# Hardware.net
KiCad netlist of a schematic drawn in Altium Designer
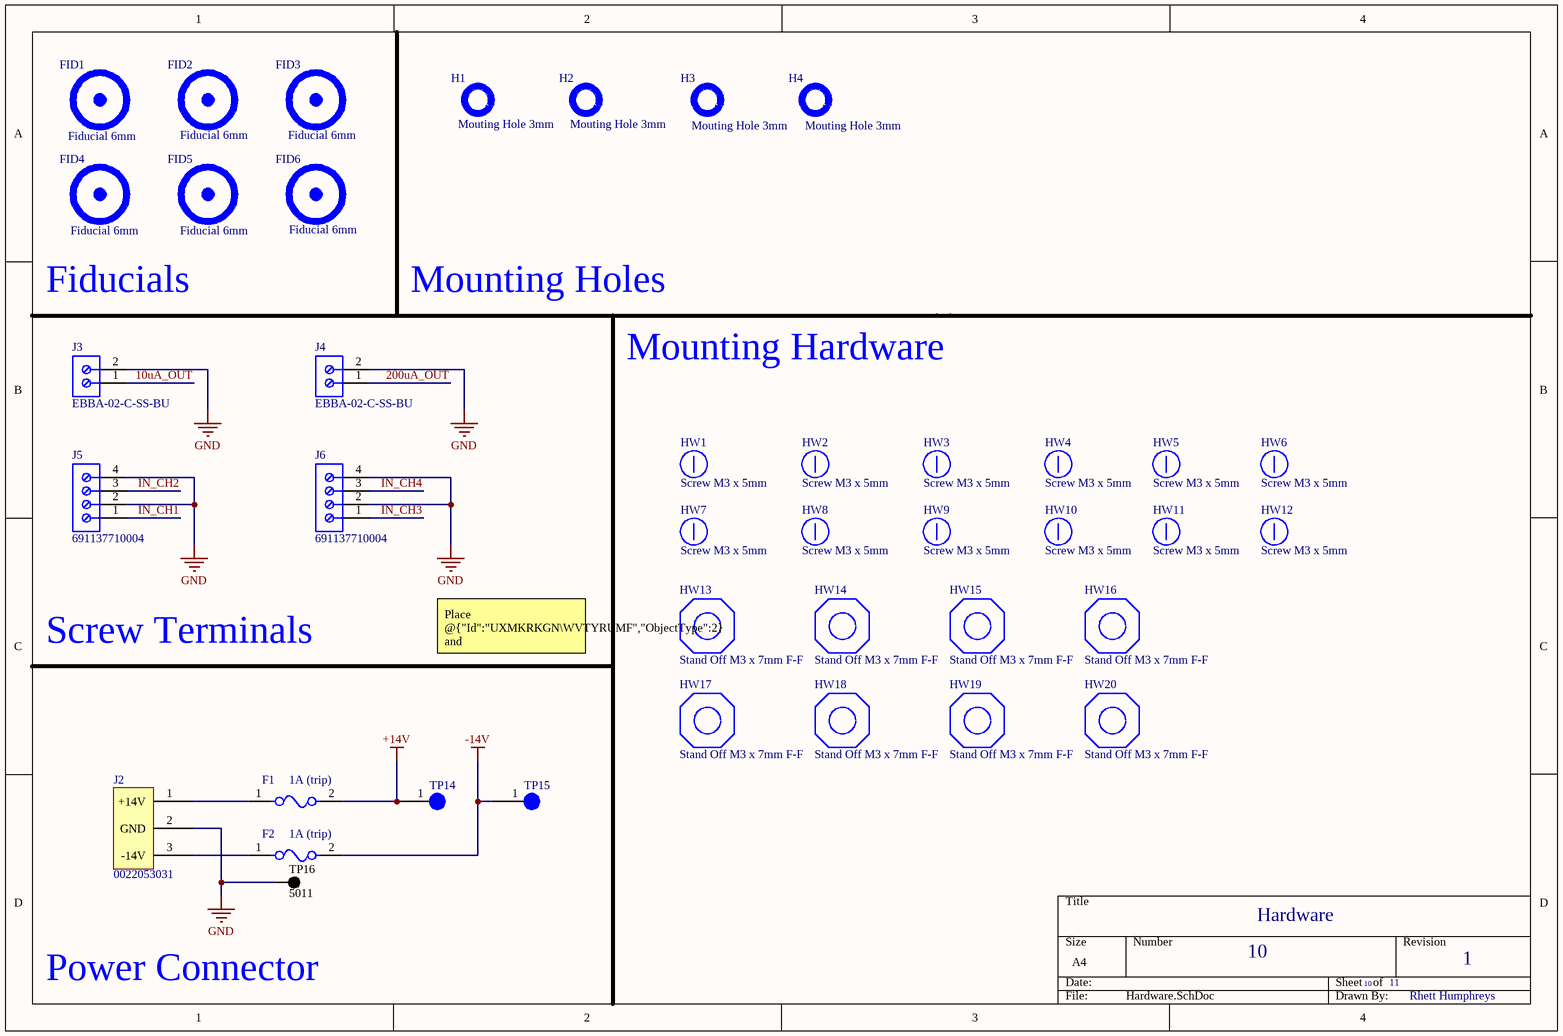
[diagram p0: Hardware.SchDoc]

(export (version "E")
  (design (tool "Eeschema 10.0.6"))
  (components
    (comp (ref "F1")
      (value "1A (trip)")
      (footprint "FP-0466-MFG")
      (description "FUSE BOARD MNT 1A 63VAC/VDC 1206")
      (fields
        (field (name "MANUFACTURER PART NUMBER") "0466001.NR")
        (field (name "MANUFACTURER") "Littelfuse Inc")
      )
      (libsource (lib "Altium Content Vault") (part "5bcf9b9f640e542cf0359d10258e979"))
    )
    (comp (ref "F2")
      (value "1A (trip)")
      (footprint "FP-0466-MFG")
      (description "FUSE BOARD MNT 1A 63VAC/VDC 1206")
      (fields
        (field (name "MANUFACTURER PART NUMBER") "0466001.NR")
        (field (name "MANUFACTURER") "Littelfuse Inc")
      )
      (libsource (lib "Altium Content Vault") (part "5bcf9b9f640e542cf0359d10258e979"))
    )
    (comp (ref "FID1")
      (value "Fiducial 6mm")
      (footprint "Fiducial 6mm")
      (libsource (lib "Master") (part "Fiducial 6mm"))
    )
    (comp (ref "FID2")
      (value "Fiducial 6mm")
      (footprint "Fiducial 6mm")
      (libsource (lib "Master") (part "Fiducial 6mm"))
    )
    (comp (ref "FID3")
      (value "Fiducial 6mm")
      (footprint "Fiducial 6mm")
      (libsource (lib "Master") (part "Fiducial 6mm"))
    )
    (comp (ref "FID4")
      (value "Fiducial 6mm")
      (footprint "Fiducial 6mm")
      (libsource (lib "Master") (part "Fiducial 6mm"))
    )
    (comp (ref "FID5")
      (value "Fiducial 6mm")
      (footprint "Fiducial 6mm")
      (libsource (lib "Master") (part "Fiducial 6mm"))
    )
    (comp (ref "FID6")
      (value "Fiducial 6mm")
      (footprint "Fiducial 6mm")
      (libsource (lib "Master") (part "Fiducial 6mm"))
    )
    (comp (ref "H1") (value "Mouting Hole 3mm") (footprint "MH3") (libsource (lib "Master") (part "MH3")))
    (comp (ref "H2") (value "Mouting Hole 3mm") (footprint "MH3") (libsource (lib "Master") (part "MH3")))
    (comp (ref "H3") (value "Mouting Hole 3mm") (footprint "MH3") (libsource (lib "Master") (part "MH3")))
    (comp (ref "H4") (value "Mouting Hole 3mm") (footprint "MH3") (libsource (lib "Master") (part "MH3")))
    (comp (ref "HW1")
      (value "Screw M3 x 5mm")
      (description "Fastener flathead M3 x 5mm")
      (libsource (lib "Master") (part "Screw M3 x 5mm"))
    )
    (comp (ref "HW2")
      (value "Screw M3 x 5mm")
      (description "Fastener flathead M3 x 5mm")
      (libsource (lib "Master") (part "Screw M3 x 5mm"))
    )
    (comp (ref "HW3")
      (value "Screw M3 x 5mm")
      (description "Fastener flathead M3 x 5mm")
      (libsource (lib "Master") (part "Screw M3 x 5mm"))
    )
    (comp (ref "HW4")
      (value "Screw M3 x 5mm")
      (description "Fastener flathead M3 x 5mm")
      (libsource (lib "Master") (part "Screw M3 x 5mm"))
    )
    (comp (ref "HW5")
      (value "Screw M3 x 5mm")
      (description "Fastener flathead M3 x 5mm")
      (libsource (lib "Master") (part "Screw M3 x 5mm"))
    )
    (comp (ref "HW6")
      (value "Screw M3 x 5mm")
      (description "Fastener flathead M3 x 5mm")
      (libsource (lib "Master") (part "Screw M3 x 5mm"))
    )
    (comp (ref "HW7")
      (value "Screw M3 x 5mm")
      (description "Fastener flathead M3 x 5mm")
      (libsource (lib "Master") (part "Screw M3 x 5mm"))
    )
    (comp (ref "HW8")
      (value "Screw M3 x 5mm")
      (description "Fastener flathead M3 x 5mm")
      (libsource (lib "Master") (part "Screw M3 x 5mm"))
    )
    (comp (ref "HW9")
      (value "Screw M3 x 5mm")
      (description "Fastener flathead M3 x 5mm")
      (libsource (lib "Master") (part "Screw M3 x 5mm"))
    )
    (comp (ref "HW10")
      (value "Screw M3 x 5mm")
      (description "Fastener flathead M3 x 5mm")
      (libsource (lib "Master") (part "Screw M3 x 5mm"))
    )
    (comp (ref "HW11")
      (value "Screw M3 x 5mm")
      (description "Fastener flathead M3 x 5mm")
      (libsource (lib "Master") (part "Screw M3 x 5mm"))
    )
    (comp (ref "HW12")
      (value "Screw M3 x 5mm")
      (description "Fastener flathead M3 x 5mm")
      (libsource (lib "Master") (part "Screw M3 x 5mm"))
    )
    (comp (ref "HW13")
      (value "Stand Off M3 x 7mm F-F")
      (description "Stand off hex M3 x 7mm")
      (libsource (lib "Master") (part "Stand Off M3 x 7mm F-F"))
    )
    (comp (ref "HW14")
      (value "Stand Off M3 x 7mm F-F")
      (description "Stand off hex M3 x 7mm")
      (libsource (lib "Master") (part "Stand Off M3 x 7mm F-F"))
    )
    (comp (ref "HW15")
      (value "Stand Off M3 x 7mm F-F")
      (description "Stand off hex M3 x 7mm")
      (libsource (lib "Master") (part "Stand Off M3 x 7mm F-F"))
    )
    (comp (ref "HW16")
      (value "Stand Off M3 x 7mm F-F")
      (description "Stand off hex M3 x 7mm")
      (libsource (lib "Master") (part "Stand Off M3 x 7mm F-F"))
    )
    (comp (ref "HW17")
      (value "Stand Off M3 x 7mm F-F")
      (description "Stand off hex M3 x 7mm")
      (libsource (lib "Master") (part "Stand Off M3 x 7mm F-F"))
    )
    (comp (ref "HW18")
      (value "Stand Off M3 x 7mm F-F")
      (description "Stand off hex M3 x 7mm")
      (libsource (lib "Master") (part "Stand Off M3 x 7mm F-F"))
    )
    (comp (ref "HW19")
      (value "Stand Off M3 x 7mm F-F")
      (description "Stand off hex M3 x 7mm")
      (libsource (lib "Master") (part "Stand Off M3 x 7mm F-F"))
    )
    (comp (ref "HW20")
      (value "Stand Off M3 x 7mm F-F")
      (description "Stand off hex M3 x 7mm")
      (libsource (lib "Master") (part "Stand Off M3 x 7mm F-F"))
    )
    (comp (ref "J2")
      (value "0022053031")
      (footprint "0022053031")
      (libsource (lib "Master") (part "0022053031"))
    )
    (comp (ref "J3")
      (value "EBBA-02-C-SS-BU")
      (footprint "TECO-282836-2_V")
      (description "Female Header, Pitch 5 mm, 1 x 2 Position, Height 10 mm, Tail Length 3.5 mm, Rohs, Bulk")
      (fields (field (name "VOLTAGE") "300V") (field (name "MANUFACTURER") "TE Connectivity"))
      (libsource (lib "Altium Content Vault") (part "CN-1P-F-TB2"))
    )
    (comp (ref "J4")
      (value "EBBA-02-C-SS-BU")
      (footprint "TECO-282836-2_V")
      (description "Female Header, Pitch 5 mm, 1 x 2 Position, Height 10 mm, Tail Length 3.5 mm, Rohs, Bulk")
      (fields (field (name "VOLTAGE") "300V") (field (name "MANUFACTURER") "TE Connectivity"))
      (libsource (lib "Altium Content Vault") (part "CN-1P-F-TB2"))
    )
    (comp (ref "J5")
      (value "691137710004")
      (footprint "691137710004")
      (libsource (lib "Altium Content Vault") (part "TBL - 1R - 04P - Screw"))
    )
    (comp (ref "J6")
      (value "691137710004")
      (footprint "691137710004")
      (libsource (lib "Altium Content Vault") (part "TBL - 1R - 04P - Screw"))
    )
    (comp (ref "TP14")
      (value "Test-Point 3mm")
      (footprint "TestPoint 3mm")
      (libsource (lib "Master") (part "Test-Point 3mm"))
    )
    (comp (ref "TP15")
      (value "Test-Point 3mm")
      (footprint "TestPoint 3mm")
      (libsource (lib "Master") (part "Test-Point 3mm"))
    )
    (comp (ref "TP16")
      (value "5011")
      (footprint "KSTN-5011_V")
      (description "Test Point, Black, Through Hole, RoHS, Bulk")
      (fields (field (name "MANUFACTURER") "Keystone"))
      (libsource (lib "Altium Content Vault") (part "TESTPOINT_BLACK"))
    )
  )
  (nets
    (net (code "1") (name "+14V") (class "Default")
      (node (ref "F1") (pin "2") (pinfunction "2_2") (pintype "passive"))
      (node (ref "TP14") (pin "1") (pintype "passive"))
    )
    (net (code "2") (name "-14V") (class "Default")
      (node (ref "F2") (pin "2") (pinfunction "2_2") (pintype "passive"))
      (node (ref "TP15") (pin "1") (pintype "passive"))
    )
    (net (code "3") (name "/10uA_OUT") (class "Default")
      (node (ref "J3") (pin "1") (pinfunction "1_1") (pintype "passive"))
    )
    (net (code "4") (name "/200uA_OUT") (class "Default")
      (node (ref "J4") (pin "1") (pinfunction "1_1") (pintype "passive"))
    )
    (net (code "5") (name "/IN_CH1") (class "Default")
      (node (ref "J5") (pin "1") (pinfunction "1_1") (pintype "passive"))
    )
    (net (code "6") (name "/IN_CH2") (class "Default")
      (node (ref "J5") (pin "3") (pinfunction "3_3") (pintype "passive"))
    )
    (net (code "7") (name "/IN_CH3") (class "Default")
      (node (ref "J6") (pin "1") (pinfunction "1_1") (pintype "passive"))
    )
    (net (code "8") (name "/IN_CH4") (class "Default")
      (node (ref "J6") (pin "3") (pinfunction "3_3") (pintype "passive"))
    )
    (net (code "9") (name "GND") (class "Default")
      (node (ref "J2") (pin "2") (pinfunction "GND_2") (pintype "passive"))
      (node (ref "J3") (pin "2") (pinfunction "2_2") (pintype "passive"))
      (node (ref "J4") (pin "2") (pinfunction "2_2") (pintype "passive"))
      (node (ref "J5") (pin "2") (pinfunction "2_2") (pintype "passive"))
      (node (ref "J5") (pin "4") (pinfunction "4_4") (pintype "passive"))
      (node (ref "J6") (pin "2") (pinfunction "2_2") (pintype "passive"))
      (node (ref "J6") (pin "4") (pinfunction "4_4") (pintype "passive"))
      (node (ref "TP16") (pin "1") (pinfunction "1_1") (pintype "passive"))
    )
    (net (code "10") (name "Net-(J2-+14V)") (class "Default")
      (node (ref "F1") (pin "1") (pinfunction "1_1") (pintype "passive"))
      (node (ref "J2") (pin "1") (pinfunction "+14V_1") (pintype "passive"))
    )
    (net (code "11") (name "Net-(J2--14V)") (class "Default")
      (node (ref "F2") (pin "1") (pinfunction "1_1") (pintype "passive"))
      (node (ref "J2") (pin "3") (pinfunction "-14V_3") (pintype "passive"))
    )
  )
)
